# 15_RK3568_SARADCGPIO.net
KiCad netlist of a schematic drawn in Altium Designer
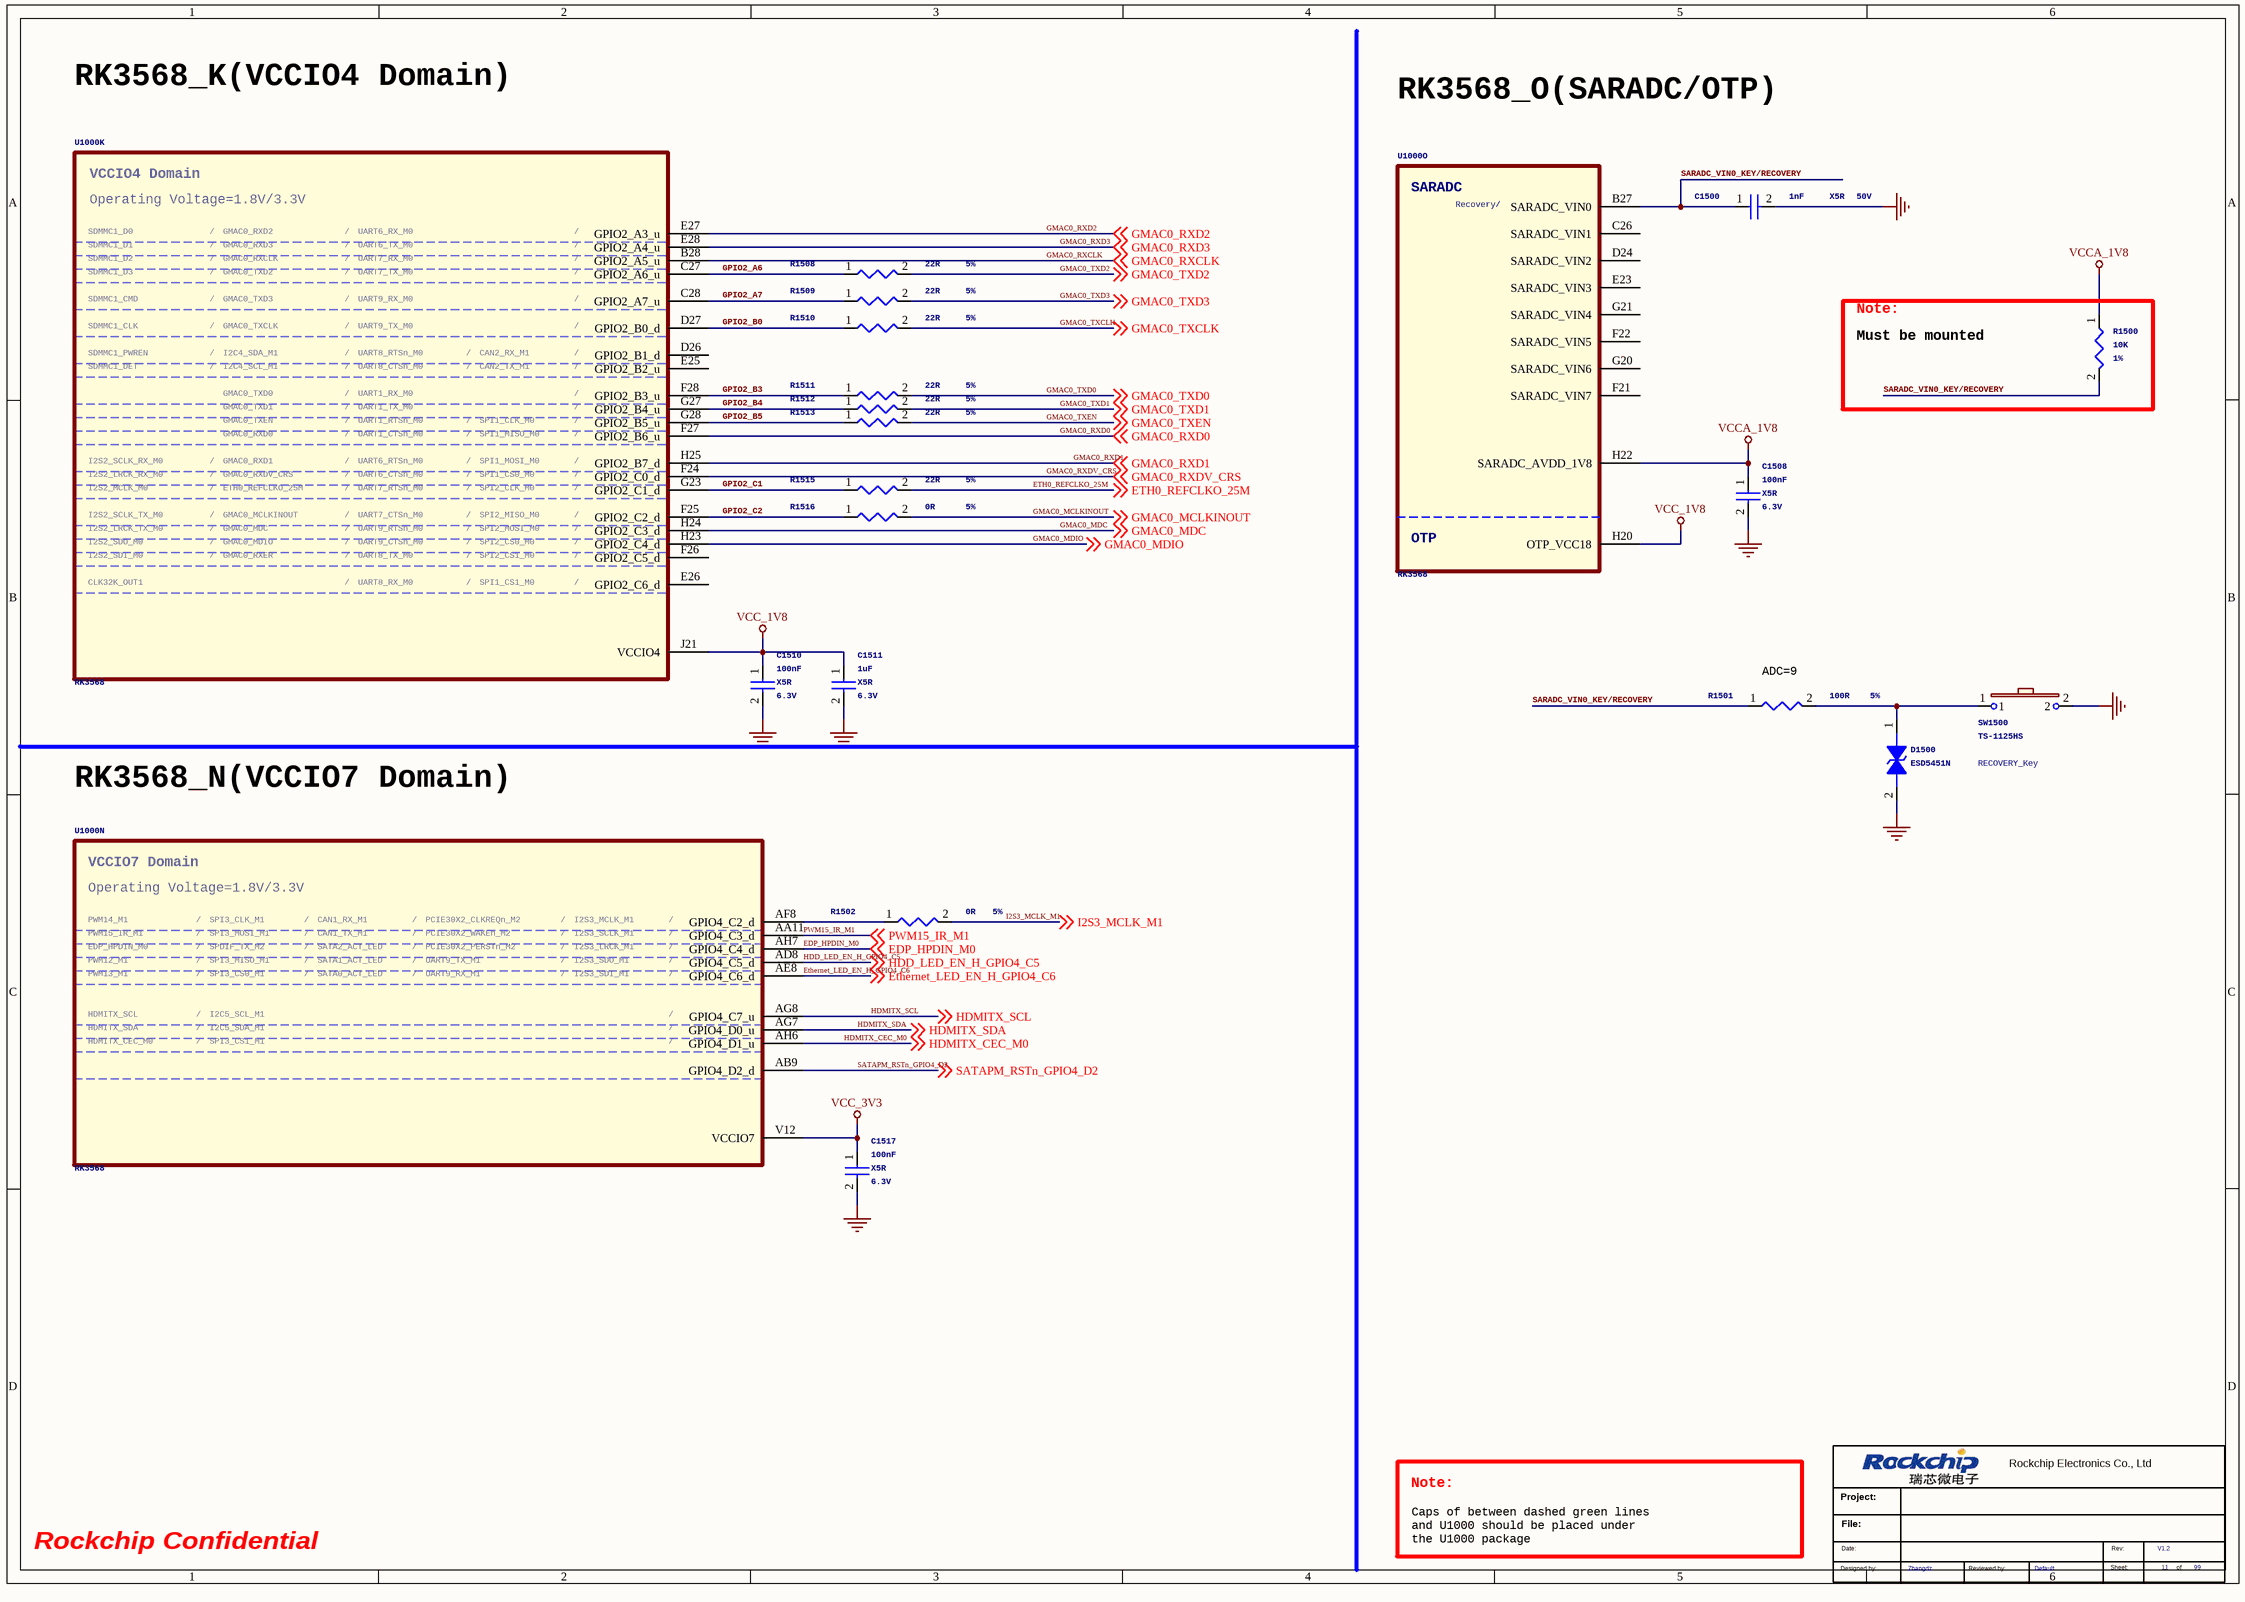
[diagram p0: 15.RK3568_SARADCGPIO.SchDoc]

(export (version "E")
  (design (tool "Eeschema 10.0.6"))
  (components
    (comp (ref "*")
      (value "Rockchip_new")
      (fields
        (field (name "SCHEMATIC PAGE COUNT") "99")
        (field (name "SCHEMATIC PAGE NUMBER") "11")
        (field (name "DESIGNER") "Zhangdz")
        (field (name "REVISION") "V1.2")
        (field (name "CHECK") "Default")
      )
      (libsource (lib "*") (part "Rockchip_new"))
    )
    (comp (ref "C1500")
      (value "1nF")
      (footprint "C0402")
      (description "cap,1.00nF,+/-10%,50V,X5R,C0402")
      (fields
        (field (name "VOLTAGE") "50V")
        (field (name "DIELECTRIC") "X5R")
        (field (name "MANUFACTURER") "TDK")
        (field (name "TOLERANCE") "10%")
        (field (name "CREATED BY") "JJJ")
      )
      (libsource (lib "*") (part "CAP NP"))
    )
    (comp (ref "C1508")
      (value "100nF")
      (footprint "C0201")
      (description "cap,100.00nF,+/-10%,6.3V,X5R,C0201")
      (fields
        (field (name "VOLTAGE") "6.3V")
        (field (name "DIELECTRIC") "X5R")
        (field (name "MANUFACTURER") "TDK")
        (field (name "TOLERANCE") "10%")
        (field (name "CREATED BY") "JJJ")
      )
      (libsource (lib "*") (part "CAP NP"))
    )
    (comp (ref "C1510")
      (value "100nF")
      (footprint "C0201")
      (description "cap,100.00nF,+/-10%,6.3V,X5R,C0201")
      (fields
        (field (name "VOLTAGE") "6.3V")
        (field (name "DIELECTRIC") "X5R")
        (field (name "MANUFACTURER") "TDK")
        (field (name "TOLERANCE") "10%")
        (field (name "CREATED BY") "JJJ")
      )
      (libsource (lib "*") (part "CAP NP"))
    )
    (comp (ref "C1511")
      (value "1uF")
      (footprint "C0402")
      (description "cap,1.00uF,+/-10%,6.3V,X5R,C0402")
      (fields
        (field (name "VOLTAGE") "6.3V")
        (field (name "DIELECTRIC") "X5R")
        (field (name "TOLERANCE") "10%")
        (field (name "MANUFACTURER") "TDK")
        (field (name "CREATED BY") "JJJ")
      )
      (libsource (lib "*") (part "CAP NP"))
    )
    (comp (ref "C1517")
      (value "100nF")
      (footprint "C0201")
      (description "cap,100.00nF,+/-10%,6.3V,X5R,C0201")
      (fields
        (field (name "VOLTAGE") "6.3V")
        (field (name "DIELECTRIC") "X5R")
        (field (name "MANUFACTURER") "TDK")
        (field (name "TOLERANCE") "10%")
        (field (name "CREATED BY") "JJJ")
      )
      (libsource (lib "*") (part "CAP NP"))
    )
    (comp (ref "D1500")
      (value "ESD5451N")
      (footprint "ESD0402")
      (description "1-Line, Bi-directional, Transient Voltage Suppressors.17.5pF.")
      (fields (field (name "MANUFACTURER") "WillSemi(韦尔半导体)") (field (name "CREATED BY") "JJJ"))
      (libsource (lib "*") (part "DIODE BI_DIR TRIG"))
    )
    (comp (ref "R1500")
      (value "10K")
      (footprint "R0402")
      (description "通用厚膜电阻,10K,+/-1%,R0402,1/16W.")
      (fields
        (field (name "TOLERANCE") "1%")
        (field (name "MANUFACTURER") "YAGEO")
        (field (name "CREATED BY") "YTL")
      )
      (libsource (lib "*") (part "RESISTOR"))
    )
    (comp (ref "R1501")
      (value "100R")
      (footprint "R0402")
      (description "通用厚膜电阻,100R,+/-5%,R0402,1/16W.")
      (fields
        (field (name "TOLERANCE") "5%")
        (field (name "MANUFACTURER") "YAGEO")
        (field (name "CREATED BY") "YTL")
      )
      (libsource (lib "*") (part "RESISTOR"))
    )
    (comp (ref "R1502")
      (value "0R")
      (footprint "R0402")
      (description "通用厚膜电阻,0R,+/-5%,R0402,1/16W.")
      (fields
        (field (name "TOLERANCE") "5%")
        (field (name "MANUFACTURER") "YAGEO")
        (field (name "CREATED BY") "YTL")
      )
      (libsource (lib "*") (part "RESISTOR"))
    )
    (comp (ref "R1508")
      (value "22R")
      (footprint "R0402")
      (description "通用厚膜电阻,22R,+/-5%,R0402,1/16W.")
      (fields
        (field (name "TOLERANCE") "5%")
        (field (name "MANUFACTURER") "YAGEO")
        (field (name "CREATED BY") "YTL")
      )
      (libsource (lib "*") (part "RESISTOR"))
    )
    (comp (ref "R1509")
      (value "22R")
      (footprint "R0402")
      (description "通用厚膜电阻,22R,+/-5%,R0402,1/16W.")
      (fields
        (field (name "TOLERANCE") "5%")
        (field (name "MANUFACTURER") "YAGEO")
        (field (name "CREATED BY") "YTL")
      )
      (libsource (lib "*") (part "RESISTOR"))
    )
    (comp (ref "R1510")
      (value "22R")
      (footprint "R0402")
      (description "通用厚膜电阻,22R,+/-5%,R0402,1/16W.")
      (fields
        (field (name "TOLERANCE") "5%")
        (field (name "MANUFACTURER") "YAGEO")
        (field (name "CREATED BY") "YTL")
      )
      (libsource (lib "*") (part "RESISTOR"))
    )
    (comp (ref "R1511")
      (value "22R")
      (footprint "R0402")
      (description "通用厚膜电阻,22R,+/-5%,R0402,1/16W.")
      (fields
        (field (name "TOLERANCE") "5%")
        (field (name "MANUFACTURER") "YAGEO")
        (field (name "CREATED BY") "YTL")
      )
      (libsource (lib "*") (part "RESISTOR"))
    )
    (comp (ref "R1512")
      (value "22R")
      (footprint "R0402")
      (description "通用厚膜电阻,22R,+/-5%,R0402,1/16W.")
      (fields
        (field (name "TOLERANCE") "5%")
        (field (name "MANUFACTURER") "YAGEO")
        (field (name "CREATED BY") "YTL")
      )
      (libsource (lib "*") (part "RESISTOR"))
    )
    (comp (ref "R1513")
      (value "22R")
      (footprint "R0402")
      (description "通用厚膜电阻,22R,+/-5%,R0402,1/16W.")
      (fields
        (field (name "TOLERANCE") "5%")
        (field (name "MANUFACTURER") "YAGEO")
        (field (name "CREATED BY") "YTL")
      )
      (libsource (lib "*") (part "RESISTOR"))
    )
    (comp (ref "R1515")
      (value "22R")
      (footprint "R0402")
      (description "通用厚膜电阻,22R,+/-5%,R0402,1/16W.")
      (fields
        (field (name "TOLERANCE") "5%")
        (field (name "MANUFACTURER") "YAGEO")
        (field (name "CREATED BY") "YTL")
      )
      (libsource (lib "*") (part "RESISTOR"))
    )
    (comp (ref "R1516")
      (value "0R")
      (footprint "R0402")
      (description "通用厚膜电阻,0R,+/-5%,R0402,1/16W.")
      (fields
        (field (name "TOLERANCE") "5%")
        (field (name "MANUFACTURER") "YAGEO")
        (field (name "CREATED BY") "YTL")
      )
      (libsource (lib "*") (part "RESISTOR"))
    )
    (comp (ref "SW1500")
      (value "TS-1125HS")
      (footprint "SW2_6R00X3R70X2R50")
      (description "2脚贴片，6MMx3.7MM按键")
      (fields
        (field (name "OPTION") "RECOVERY_Key")
        (field (name "MANUFACTURER") "褀华电子")
        (field (name "CREATED BY") "YWQ")
      )
      (libsource (lib "*") (part "KEY_2PIN"))
    )
    (comp (ref "U1000")
      (value "RK3568")
      (footprint "BGA636_19R00X19R00X1R20")
      (description "ROCKCHIP SOC")
      (fields (field (name "MANUFACTURER") "Rockchip (瑞芯微)") (field (name "CREATED BY") "JJJ"))
      (libsource (lib "*") (part "SOC_RK3568"))
    )
  )
  (nets
    (net (code "1") (name "/GPIO2_A6") (class "Default")
      (node (ref "R1508") (pin "1") (pinfunction "1_1") (pintype "passive"))
      (node (ref "U1000") (pin "C27") (pinfunction "GPIO2_A6_u_C27") (pintype "passive"))
    )
    (net (code "2") (name "/GPIO2_A7") (class "Default")
      (node (ref "R1509") (pin "1") (pinfunction "1_1") (pintype "passive"))
      (node (ref "U1000") (pin "C28") (pinfunction "GPIO2_A7_u_C28") (pintype "passive"))
    )
    (net (code "3") (name "/GPIO2_B0") (class "Default")
      (node (ref "R1510") (pin "1") (pinfunction "1_1") (pintype "passive"))
      (node (ref "U1000") (pin "D27") (pinfunction "GPIO2_B0_d_D27") (pintype "passive"))
    )
    (net (code "4") (name "/GPIO2_B3") (class "Default")
      (node (ref "R1511") (pin "1") (pinfunction "1_1") (pintype "passive"))
      (node (ref "U1000") (pin "F28") (pinfunction "GPIO2_B3_u_F28") (pintype "passive"))
    )
    (net (code "5") (name "/GPIO2_B4") (class "Default")
      (node (ref "R1512") (pin "1") (pinfunction "1_1") (pintype "passive"))
      (node (ref "U1000") (pin "G27") (pinfunction "GPIO2_B4_u_G27") (pintype "passive"))
    )
    (net (code "6") (name "/GPIO2_B5") (class "Default")
      (node (ref "R1513") (pin "1") (pinfunction "1_1") (pintype "passive"))
      (node (ref "U1000") (pin "G28") (pinfunction "GPIO2_B5_u_G28") (pintype "passive"))
    )
    (net (code "7") (name "/GPIO2_C1") (class "Default")
      (node (ref "R1515") (pin "1") (pinfunction "1_1") (pintype "passive"))
      (node (ref "U1000") (pin "G23") (pinfunction "GPIO2_C1_d_G23") (pintype "passive"))
    )
    (net (code "8") (name "/GPIO2_C2") (class "Default")
      (node (ref "R1516") (pin "1") (pinfunction "1_1") (pintype "passive"))
      (node (ref "U1000") (pin "F25") (pinfunction "GPIO2_C2_d_F25") (pintype "passive"))
    )
    (net (code "9") (name "/SARADC_VIN0_KEY{slash}RECOVERY") (class "Default")
      (node (ref "C1500") (pin "1") (pinfunction "1_1") (pintype "passive"))
      (node (ref "R1500") (pin "2") (pinfunction "2_2") (pintype "passive"))
      (node (ref "R1501") (pin "1") (pinfunction "1_1") (pintype "passive"))
      (node (ref "U1000") (pin "B27") (pinfunction "SARADC_VIN0_B27") (pintype "passive"))
    )
    (net (code "10") (name "EDP_HPDIN_M0") (class "Default")
      (node (ref "U1000") (pin "AH7") (pinfunction "GPIO4_C4_d_AH7") (pintype "passive"))
    )
    (net (code "11") (name "ETH0_REFCLKO_25M") (class "Default")
      (node (ref "R1515") (pin "2") (pinfunction "2_2") (pintype "passive"))
    )
    (net (code "12") (name "Ethernet_LED_EN_H_GPIO4_C6") (class "Default")
      (node (ref "U1000") (pin "AE8") (pinfunction "GPIO4_C6_d_AE8") (pintype "passive"))
    )
    (net (code "13") (name "GMAC0_MCLKINOUT") (class "Default")
      (node (ref "R1516") (pin "2") (pinfunction "2_2") (pintype "passive"))
    )
    (net (code "14") (name "GMAC0_MDC") (class "Default")
      (node (ref "U1000") (pin "H24") (pinfunction "GPIO2_C3_d_H24") (pintype "passive"))
    )
    (net (code "15") (name "GMAC0_MDIO") (class "Default")
      (node (ref "U1000") (pin "H23") (pinfunction "GPIO2_C4_d_H23") (pintype "passive"))
    )
    (net (code "16") (name "GMAC0_RXCLK") (class "Default")
      (node (ref "U1000") (pin "B28") (pinfunction "GPIO2_A5_u_B28") (pintype "passive"))
    )
    (net (code "17") (name "GMAC0_RXD0") (class "Default")
      (node (ref "U1000") (pin "F27") (pinfunction "GPIO2_B6_u_F27") (pintype "passive"))
    )
    (net (code "18") (name "GMAC0_RXD1") (class "Default")
      (node (ref "U1000") (pin "H25") (pinfunction "GPIO2_B7_d_H25") (pintype "passive"))
    )
    (net (code "19") (name "GMAC0_RXD2") (class "Default")
      (node (ref "U1000") (pin "E27") (pinfunction "GPIO2_A3_u_E27") (pintype "passive"))
    )
    (net (code "20") (name "GMAC0_RXD3") (class "Default")
      (node (ref "U1000") (pin "E28") (pinfunction "GPIO2_A4_u_E28") (pintype "passive"))
    )
    (net (code "21") (name "GMAC0_RXDV_CRS") (class "Default")
      (node (ref "U1000") (pin "F24") (pinfunction "GPIO2_C0_d_F24") (pintype "passive"))
    )
    (net (code "22") (name "GMAC0_TXCLK") (class "Default")
      (node (ref "R1510") (pin "2") (pinfunction "2_2") (pintype "passive"))
    )
    (net (code "23") (name "GMAC0_TXD0") (class "Default")
      (node (ref "R1511") (pin "2") (pinfunction "2_2") (pintype "passive"))
    )
    (net (code "24") (name "GMAC0_TXD1") (class "Default")
      (node (ref "R1512") (pin "2") (pinfunction "2_2") (pintype "passive"))
    )
    (net (code "25") (name "GMAC0_TXD2") (class "Default")
      (node (ref "R1508") (pin "2") (pinfunction "2_2") (pintype "passive"))
    )
    (net (code "26") (name "GMAC0_TXD3") (class "Default")
      (node (ref "R1509") (pin "2") (pinfunction "2_2") (pintype "passive"))
    )
    (net (code "27") (name "GMAC0_TXEN") (class "Default")
      (node (ref "R1513") (pin "2") (pinfunction "2_2") (pintype "passive"))
    )
    (net (code "28") (name "GND") (class "Default")
      (node (ref "C1500") (pin "2") (pinfunction "2_2") (pintype "passive"))
      (node (ref "C1508") (pin "2") (pinfunction "2_2") (pintype "passive"))
      (node (ref "C1510") (pin "2") (pinfunction "2_2") (pintype "passive"))
      (node (ref "C1511") (pin "2") (pinfunction "2_2") (pintype "passive"))
      (node (ref "C1517") (pin "2") (pinfunction "2_2") (pintype "passive"))
      (node (ref "D1500") (pin "2") (pinfunction "2_2") (pintype "passive"))
      (node (ref "SW1500") (pin "2") (pinfunction "2_2") (pintype "passive"))
    )
    (net (code "29") (name "HDD_LED_EN_H_GPIO4_C5") (class "Default")
      (node (ref "U1000") (pin "AD8") (pinfunction "GPIO4_C5_d_AD8") (pintype "passive"))
    )
    (net (code "30") (name "HDMITX_CEC_M0") (class "Default")
      (node (ref "U1000") (pin "AH6") (pinfunction "GPIO4_D1_u_AH6") (pintype "passive"))
    )
    (net (code "31") (name "HDMITX_SCL") (class "Default")
      (node (ref "U1000") (pin "AG8") (pinfunction "GPIO4_C7_u_AG8") (pintype "passive"))
    )
    (net (code "32") (name "HDMITX_SDA") (class "Default")
      (node (ref "U1000") (pin "AG7") (pinfunction "GPIO4_D0_u_AG7") (pintype "passive"))
    )
    (net (code "33") (name "I2S3_MCLK_M1") (class "Default")
      (node (ref "R1502") (pin "2") (pinfunction "2_2") (pintype "passive"))
    )
    (net (code "34") (name "Net-(D1500-Pad1)") (class "Default")
      (node (ref "D1500") (pin "1") (pinfunction "1_1") (pintype "passive"))
      (node (ref "R1501") (pin "2") (pinfunction "2_2") (pintype "passive"))
      (node (ref "SW1500") (pin "1") (pinfunction "1_1") (pintype "passive"))
    )
    (net (code "35") (name "Net-(U1000N-GPIO4_C2_d)") (class "Default")
      (node (ref "R1502") (pin "1") (pinfunction "1_1") (pintype "passive"))
      (node (ref "U1000") (pin "AF8") (pinfunction "GPIO4_C2_d_AF8") (pintype "passive"))
    )
    (net (code "36") (name "PWM15_IR_M1") (class "Default")
      (node (ref "U1000") (pin "AA11") (pinfunction "GPIO4_C3_d_AA11") (pintype "passive"))
    )
    (net (code "37") (name "SATAPM_RSTn_GPIO4_D2") (class "Default")
      (node (ref "U1000") (pin "AB9") (pinfunction "GPIO4_D2_d_AB9") (pintype "passive"))
    )
    (net (code "38") (name "VCCA_1V8") (class "Default")
      (node (ref "C1508") (pin "1") (pinfunction "1_1") (pintype "passive"))
      (node (ref "R1500") (pin "1") (pinfunction "1_1") (pintype "passive"))
      (node (ref "U1000") (pin "H22") (pinfunction "SARADC_AVDD_1V8_H22") (pintype "passive"))
    )
    (net (code "39") (name "VCC_1V8") (class "Default")
      (node (ref "C1510") (pin "1") (pinfunction "1_1") (pintype "passive"))
      (node (ref "C1511") (pin "1") (pinfunction "1_1") (pintype "passive"))
      (node (ref "U1000") (pin "H20") (pinfunction "OTP_VCC18_H20") (pintype "passive"))
      (node (ref "U1000") (pin "J21") (pinfunction "VCCIO4_J21") (pintype "passive"))
    )
    (net (code "40") (name "VCC_3V3") (class "Default")
      (node (ref "C1517") (pin "1") (pinfunction "1_1") (pintype "passive"))
      (node (ref "U1000") (pin "V12") (pinfunction "VCCIO7_V12") (pintype "passive"))
    )
    (net (code "41") (name "unconnected-(U1000K-GPIO2_B1_d-PadD26)") (class "Default")
      (node (ref "U1000") (pin "D26") (pinfunction "GPIO2_B1_d_D26") (pintype "passive"))
    )
    (net (code "42") (name "unconnected-(U1000K-GPIO2_B2_u-PadE25)") (class "Default")
      (node (ref "U1000") (pin "E25") (pinfunction "GPIO2_B2_u_E25") (pintype "passive"))
    )
    (net (code "43") (name "unconnected-(U1000K-GPIO2_C5_d-PadF26)") (class "Default")
      (node (ref "U1000") (pin "F26") (pinfunction "GPIO2_C5_d_F26") (pintype "passive"))
    )
    (net (code "44") (name "unconnected-(U1000K-GPIO2_C6_d-PadE26)") (class "Default")
      (node (ref "U1000") (pin "E26") (pinfunction "GPIO2_C6_d_E26") (pintype "passive"))
    )
    (net (code "45") (name "unconnected-(U1000O-SARADC_VIN1-PadC26)") (class "Default")
      (node (ref "U1000") (pin "C26") (pinfunction "SARADC_VIN1_C26") (pintype "passive"))
    )
    (net (code "46") (name "unconnected-(U1000O-SARADC_VIN2-PadD24)") (class "Default")
      (node (ref "U1000") (pin "D24") (pinfunction "SARADC_VIN2_D24") (pintype "passive"))
    )
    (net (code "47") (name "unconnected-(U1000O-SARADC_VIN3-PadE23)") (class "Default")
      (node (ref "U1000") (pin "E23") (pinfunction "SARADC_VIN3_E23") (pintype "passive"))
    )
    (net (code "48") (name "unconnected-(U1000O-SARADC_VIN4-PadG21)") (class "Default")
      (node (ref "U1000") (pin "G21") (pinfunction "SARADC_VIN4_G21") (pintype "passive"))
    )
    (net (code "49") (name "unconnected-(U1000O-SARADC_VIN5-PadF22)") (class "Default")
      (node (ref "U1000") (pin "F22") (pinfunction "SARADC_VIN5_F22") (pintype "passive"))
    )
    (net (code "50") (name "unconnected-(U1000O-SARADC_VIN6-PadG20)") (class "Default")
      (node (ref "U1000") (pin "G20") (pinfunction "SARADC_VIN6_G20") (pintype "passive"))
    )
    (net (code "51") (name "unconnected-(U1000O-SARADC_VIN7-PadF21)") (class "Default")
      (node (ref "U1000") (pin "F21") (pinfunction "SARADC_VIN7_F21") (pintype "passive"))
    )
  )
)
